# triac.net
KiCad netlist of a schematic drawn in Altium Designer
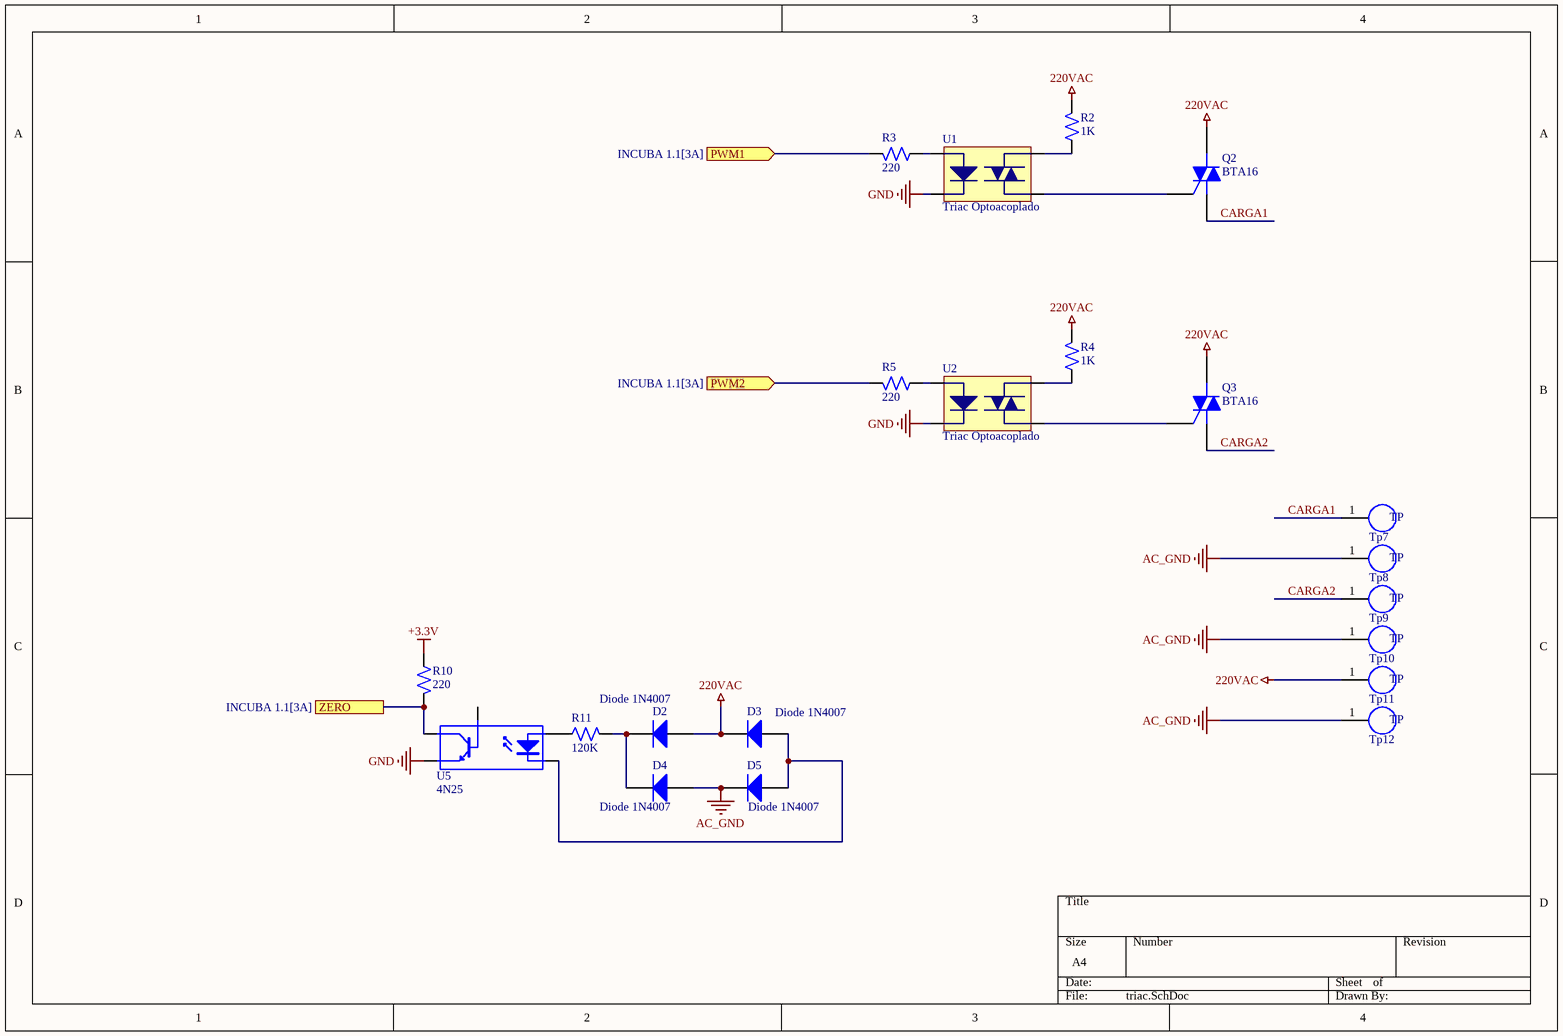
[diagram p0: triac.SchDoc]

(export (version "E")
  (design (tool "Eeschema 10.0.6"))
  (components
    (comp (ref "D2")
      (value "Diode 1N4007")
      (footprint "DO-214AC")
      (description "1 Amp General Purpose Rectifier")
      (fields (field (name "PUBLISHER") "Altium Limited"))
      (libsource (lib "Miscellaneous Devices") (part "Diode 1N4007"))
    )
    (comp (ref "D3")
      (value "Diode 1N4007")
      (footprint "DO-214AC")
      (description "1 Amp General Purpose Rectifier")
      (fields (field (name "PUBLISHER") "Altium Limited"))
      (libsource (lib "Miscellaneous Devices") (part "Diode 1N4007"))
    )
    (comp (ref "D4")
      (value "Diode 1N4007")
      (footprint "DO-214AC")
      (description "1 Amp General Purpose Rectifier")
      (fields (field (name "PUBLISHER") "Altium Limited"))
      (libsource (lib "Miscellaneous Devices") (part "Diode 1N4007"))
    )
    (comp (ref "D5")
      (value "Diode 1N4007")
      (footprint "DO-214AC")
      (description "1 Amp General Purpose Rectifier")
      (fields (field (name "PUBLISHER") "Altium Limited"))
      (libsource (lib "Miscellaneous Devices") (part "Diode 1N4007"))
    )
    (comp (ref "Q2")
      (value "BTA16")
      (footprint "TO-220")
      (description "Triac (40 Amps 600V)")
      (libsource (lib "daniel") (part "BTA41600B"))
    )
    (comp (ref "Q3")
      (value "BTA16")
      (footprint "TO-220")
      (description "Triac (40 Amps 600V)")
      (libsource (lib "daniel") (part "BTA41600B"))
    )
    (comp (ref "R2")
      (value "1K")
      (footprint "0805")
      (description "Resistencia  de con varios Footprint")
      (fields (field (name "Comment") "Resistencia"))
      (libsource (lib "daniel") (part "Resistencia"))
    )
    (comp (ref "R3")
      (value "220")
      (footprint "0805")
      (description "Resistencia  de con varios Footprint")
      (fields (field (name "Comment") "Resistencia"))
      (libsource (lib "daniel") (part "Resistencia"))
    )
    (comp (ref "R4")
      (value "1K")
      (footprint "0805")
      (description "Resistencia  de con varios Footprint")
      (fields (field (name "Comment") "Resistencia"))
      (libsource (lib "daniel") (part "Resistencia"))
    )
    (comp (ref "R5")
      (value "220")
      (footprint "0805")
      (description "Resistencia  de con varios Footprint")
      (fields (field (name "Comment") "Resistencia"))
      (libsource (lib "daniel") (part "Resistencia"))
    )
    (comp (ref "R10")
      (value "220")
      (footprint "0805")
      (description "Resistencia  de con varios Footprint")
      (fields (field (name "Comment") "Resistencia"))
      (libsource (lib "daniel") (part "Resistencia"))
    )
    (comp (ref "R11")
      (value "120K")
      (footprint "0805")
      (description "Resistencia  de con varios Footprint")
      (fields (field (name "Comment") "Resistencia"))
      (libsource (lib "daniel") (part "Resistencia"))
    )
    (comp (ref "Tp7")
      (value "Testpoint")
      (footprint "Testpoint")
      (description "Tespoint")
      (libsource (lib "daniel") (part "Testpoint"))
    )
    (comp (ref "Tp8")
      (value "Testpoint")
      (footprint "Testpoint")
      (description "Tespoint")
      (libsource (lib "daniel") (part "Testpoint"))
    )
    (comp (ref "Tp9")
      (value "Testpoint")
      (footprint "Testpoint")
      (description "Tespoint")
      (libsource (lib "daniel") (part "Testpoint"))
    )
    (comp (ref "Tp10")
      (value "Testpoint")
      (footprint "Testpoint")
      (description "Tespoint")
      (libsource (lib "daniel") (part "Testpoint"))
    )
    (comp (ref "Tp11")
      (value "Testpoint")
      (footprint "Testpoint")
      (description "Tespoint")
      (libsource (lib "daniel") (part "Testpoint"))
    )
    (comp (ref "Tp12")
      (value "Testpoint")
      (footprint "Testpoint")
      (description "Tespoint")
      (libsource (lib "daniel") (part "Testpoint"))
    )
    (comp (ref "U1")
      (value "Triac Optoacoplado")
      (footprint "DIP6")
      (libsource (lib "daniel") (part "MOC3040"))
    )
    (comp (ref "U2")
      (value "Triac Optoacoplado")
      (footprint "DIP6")
      (libsource (lib "daniel") (part "MOC3040"))
    )
    (comp (ref "U5")
      (value "4N25")
      (footprint "DIP6")
      (description "5 Pin Mini Flat Pack Optocoupler")
      (fields (field (name "PUBLISHER") "Altium Limited"))
      (libsource (lib "daniel") (part "4N25"))
    )
  )
  (nets
    (net (code "1") (name "+3.3V") (class "Default")
      (node (ref "R10") (pin "1") (pinfunction "1_1") (pintype "passive"))
    )
    (net (code "2") (name "/CARGA1") (class "Default")
      (node (ref "Q2") (pin "1") (pinfunction "M1_1") (pintype "passive"))
      (node (ref "Tp7") (pin "1") (pinfunction "TP_1") (pintype "passive"))
    )
    (net (code "3") (name "/CARGA2") (class "Default")
      (node (ref "Q3") (pin "1") (pinfunction "M1_1") (pintype "passive"))
      (node (ref "Tp9") (pin "1") (pinfunction "TP_1") (pintype "passive"))
    )
    (net (code "4") (name "/PWM1") (class "Default")
      (node (ref "R3") (pin "2") (pinfunction "2_2") (pintype "passive"))
    )
    (net (code "5") (name "/PWM2") (class "Default")
      (node (ref "R5") (pin "2") (pinfunction "2_2") (pintype "passive"))
    )
    (net (code "6") (name "/ZERO") (class "Default")
      (node (ref "R10") (pin "2") (pinfunction "2_2") (pintype "passive"))
      (node (ref "U5") (pin "5") (pinfunction "C_5") (pintype "passive"))
    )
    (net (code "7") (name "220VAC") (class "Default")
      (node (ref "D2") (pin "1") (pinfunction "A_1") (pintype "passive"))
      (node (ref "D3") (pin "2") (pinfunction "K_2") (pintype "passive"))
      (node (ref "Q2") (pin "2") (pinfunction "M2_2") (pintype "passive"))
      (node (ref "Q3") (pin "2") (pinfunction "M2_2") (pintype "passive"))
      (node (ref "R2") (pin "2") (pinfunction "2_2") (pintype "passive"))
      (node (ref "R4") (pin "2") (pinfunction "2_2") (pintype "passive"))
      (node (ref "Tp11") (pin "1") (pinfunction "TP_1") (pintype "passive"))
    )
    (net (code "8") (name "AC_GND") (class "Default")
      (node (ref "D4") (pin "1") (pinfunction "A_1") (pintype "passive"))
      (node (ref "D5") (pin "2") (pinfunction "K_2") (pintype "passive"))
      (node (ref "Tp10") (pin "1") (pinfunction "TP_1") (pintype "passive"))
      (node (ref "Tp12") (pin "1") (pinfunction "TP_1") (pintype "passive"))
      (node (ref "Tp8") (pin "1") (pinfunction "TP_1") (pintype "passive"))
    )
    (net (code "9") (name "GND") (class "Default")
      (node (ref "U1") (pin "2") (pinfunction "2_2") (pintype "passive"))
      (node (ref "U2") (pin "2") (pinfunction "2_2") (pintype "passive"))
      (node (ref "U5") (pin "4") (pinfunction "E_4") (pintype "passive"))
    )
    (net (code "10") (name "Net-(D2-K)") (class "Default")
      (node (ref "D2") (pin "2") (pinfunction "K_2") (pintype "passive"))
      (node (ref "D4") (pin "2") (pinfunction "K_2") (pintype "passive"))
      (node (ref "R11") (pin "2") (pinfunction "2_2") (pintype "passive"))
    )
    (net (code "11") (name "Net-(D3-A)") (class "Default")
      (node (ref "D3") (pin "1") (pinfunction "A_1") (pintype "passive"))
      (node (ref "D5") (pin "1") (pinfunction "A_1") (pintype "passive"))
      (node (ref "U5") (pin "2") (pinfunction "K_2") (pintype "passive"))
    )
    (net (code "12") (name "Net-(Q2-G)") (class "Default")
      (node (ref "Q2") (pin "3") (pinfunction "G_3") (pintype "passive"))
      (node (ref "U1") (pin "4") (pinfunction "4_4") (pintype "passive"))
    )
    (net (code "13") (name "Net-(Q3-G)") (class "Default")
      (node (ref "Q3") (pin "3") (pinfunction "G_3") (pintype "passive"))
      (node (ref "U2") (pin "4") (pinfunction "4_4") (pintype "passive"))
    )
    (net (code "14") (name "Net-(R2-Pad1)") (class "Default")
      (node (ref "R2") (pin "1") (pinfunction "1_1") (pintype "passive"))
      (node (ref "U1") (pin "6") (pinfunction "6_6") (pintype "passive"))
    )
    (net (code "15") (name "Net-(R3-Pad1)") (class "Default")
      (node (ref "R3") (pin "1") (pinfunction "1_1") (pintype "passive"))
      (node (ref "U1") (pin "1") (pinfunction "1_1") (pintype "passive"))
    )
    (net (code "16") (name "Net-(R4-Pad1)") (class "Default")
      (node (ref "R4") (pin "1") (pinfunction "1_1") (pintype "passive"))
      (node (ref "U2") (pin "6") (pinfunction "6_6") (pintype "passive"))
    )
    (net (code "17") (name "Net-(R5-Pad1)") (class "Default")
      (node (ref "R5") (pin "1") (pinfunction "1_1") (pintype "passive"))
      (node (ref "U2") (pin "1") (pinfunction "1_1") (pintype "passive"))
    )
    (net (code "18") (name "Net-(U5-A)") (class "Default")
      (node (ref "R11") (pin "1") (pinfunction "1_1") (pintype "passive"))
      (node (ref "U5") (pin "1") (pinfunction "A_1") (pintype "passive"))
    )
    (net (code "19") (name "unconnected-(U5-B-Pad6)") (class "Default")
      (node (ref "U5") (pin "6") (pinfunction "B_6") (pintype "passive"))
    )
  )
)
